# current-source.net
KiCad netlist of a schematic drawn in Altium Designer
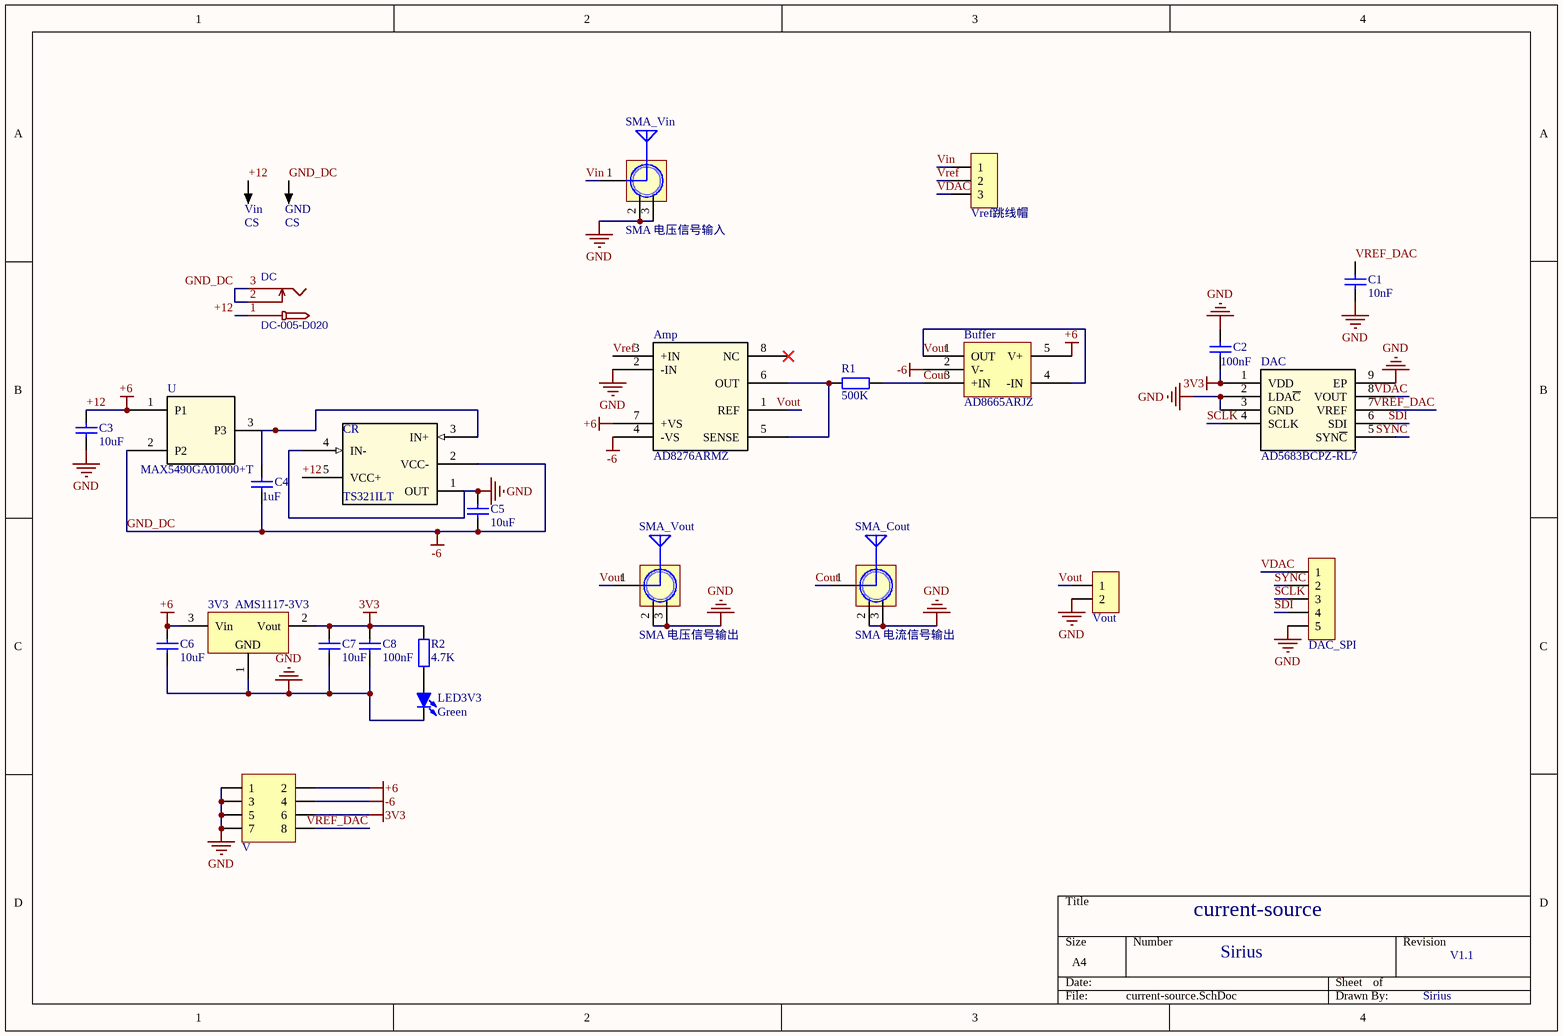
[diagram p0: current-source.SchDoc]

(export (version "E")
  (design (tool "Eeschema 10.0.6"))
  (components
    (comp (ref "3V3")
      (value "AMS1117-3V3")
      (footprint "SOT89_L")
      (description "三端稳压芯片")
      (libsource (lib "0.7 - 电源类芯片") (part "AMS1117_SOT89"))
    )
    (comp (ref "Amp")
      (value "AD8276ARMZ")
      (footprint "RM_8_ADI-L")
      (description "差动放大器")
      (fields
        (field (name "MANUFACTURER_PART_NUMBER") "AD8276ARZ")
        (field (name "COPYRIGHT") "Copyright (C) 2022 Ultra Librarian. All rights reserved.")
      )
      (libsource (lib "Extra Sch") (part "AD8276"))
    )
    (comp (ref "Buffer")
      (value "AD8665ARJZ")
      (footprint "UJ_5_ADI-L")
      (description "低偏置电流运放")
      (libsource (lib "Extra Sch") (part "AD8665ARJZ"))
    )
    (comp (ref "C1")
      (value "10nF")
      (footprint "C0603_L")
      (description "贴片电容")
      (libsource (lib "0.1 - 电阻-电容-电感-晶振-晶体-磁珠-电位器") (part "C"))
    )
    (comp (ref "C2")
      (value "100nF")
      (footprint "C0603_L")
      (description "贴片电容")
      (libsource (lib "0.1 - 电阻-电容-电感-晶振-晶体-磁珠-电位器") (part "C"))
    )
    (comp (ref "C3")
      (value "10uF")
      (footprint "C0603_L")
      (description "贴片电容")
      (libsource (lib "0.1 - 电阻-电容-电感-晶振-晶体-磁珠-电位器") (part "C"))
    )
    (comp (ref "C4")
      (value "1uF")
      (footprint "C0603_L")
      (description "贴片电容")
      (libsource (lib "0.1 - 电阻-电容-电感-晶振-晶体-磁珠-电位器") (part "C"))
    )
    (comp (ref "C5")
      (value "10uF")
      (footprint "C0603_L")
      (description "贴片电容")
      (libsource (lib "0.1 - 电阻-电容-电感-晶振-晶体-磁珠-电位器") (part "C"))
    )
    (comp (ref "C6")
      (value "10uF")
      (footprint "C0603_L")
      (description "贴片电容")
      (libsource (lib "0.1 - 电阻-电容-电感-晶振-晶体-磁珠-电位器") (part "C"))
    )
    (comp (ref "C7")
      (value "10uF")
      (footprint "C0603_L")
      (description "贴片电容")
      (libsource (lib "0.1 - 电阻-电容-电感-晶振-晶体-磁珠-电位器") (part "C"))
    )
    (comp (ref "C8")
      (value "100nF")
      (footprint "C0603_L")
      (description "贴片电容")
      (libsource (lib "0.1 - 电阻-电容-电感-晶振-晶体-磁珠-电位器") (part "C"))
    )
    (comp (ref "CR")
      (value "TS321ILT")
      (footprint "SOT23-5_STM-L")
      (description "Amp")
      (fields (field (name "COPYRIGHT") "Copyright (C) 2022 Ultra Librarian. All rights reserved."))
      (libsource (lib "Extra Sch") (part "TS321ILT"))
    )
    (comp (ref "DAC")
      (value "AD5683BCPZ-RL7")
      (footprint "CP_8_10_ADI-L")
      (description "16bit DAC")
      (fields (field (name "COPYRIGHT") "Copyright (C) 2022 Ultra Librarian. All rights reserved."))
      (libsource (lib "Extra Sch") (part "AD5683BCPZ-RL7"))
    )
    (comp (ref "DAC_SPI")
      (value "HDR-1X5")
      (footprint "XH2.54-WI-5P")
      (description "5P接插件")
      (libsource (lib "5.5 - 2.54mm(100mil)连接器(XH2.54)") (part "Header 5"))
    )
    (comp (ref "DC")
      (value "DC-005-D020")
      (footprint "DC-IN-TH_G-SWITCH_DC-005-D020")
      (fields (field (name "BOM_SUPPLIER PART") "C963210") (field (name "CONTRIBUTOR") "LCSC"))
      (libsource (lib "Extra Sch") (part "DC-005-D020"))
    )
    (comp (ref "GND")
      (value "CS")
      (footprint "R100")
      (description "探针焊盘")
      (libsource (lib "0.5 - 按键-开关-蜂鸣器-保险丝-电池-测试点-Mark点") (part "CS"))
    )
    (comp (ref "LED3V3")
      (value "Green")
      (footprint "LED0603_G")
      (description "贴片LED")
      (libsource (lib "0.3 - LED发光二极管-IR二极管_接收管-光耦") (part "LED-SMD"))
    )
    (comp (ref "R1")
      (value "500K")
      (footprint "R0603_L")
      (description "贴片电阻")
      (libsource (lib "0.1 - 电阻-电容-电感-晶振-晶体-磁珠-电位器") (part "R"))
    )
    (comp (ref "R2")
      (value "4.7K")
      (footprint "R0603_L")
      (description "贴片电阻")
      (libsource (lib "0.1 - 电阻-电容-电感-晶振-晶体-磁珠-电位器") (part "R"))
    )
    (comp (ref "SMA_Cout")
      (value "SMA 电流信号输出")
      (footprint "SMA_FR")
      (description "SMA-2.4G射频天线接口")
      (libsource (lib "1.7 - WiFi天线-SMA射频座") (part "SMA"))
    )
    (comp (ref "SMA_Vin")
      (value "SMA 电压信号输入")
      (footprint "SMA_FR")
      (description "SMA-2.4G射频天线接口")
      (libsource (lib "1.7 - WiFi天线-SMA射频座") (part "SMA"))
    )
    (comp (ref "SMA_Vout")
      (value "SMA 电压信号输出")
      (footprint "SMA_FR")
      (description "SMA-2.4G射频天线接口")
      (libsource (lib "1.7 - WiFi天线-SMA射频座") (part "SMA"))
    )
    (comp (ref "U")
      (value "MAX5490GA01000+T")
      (footprint "21-0051H_MXM-L")
      (description "分压器")
      (fields (field (name "COPYRIGHT") "Copyright (C) 2022 Ultra Librarian. All rights reserved."))
      (libsource (lib "Extra Sch") (part "MAX5490GA01000+T"))
    )
    (comp (ref "V")
      (value "Header 4X2")
      (footprint "HDR2.54-LI-2x4P")
      (description "4*2P接插件")
      (libsource (lib "5.5 - 2.54mm(100mil)连接器(XH2.54)") (part "Header 4X2"))
    )
    (comp (ref "Vin")
      (value "CS")
      (footprint "R100")
      (description "探针焊盘")
      (libsource (lib "0.5 - 按键-开关-蜂鸣器-保险丝-电池-测试点-Mark点") (part "CS"))
    )
    (comp (ref "Vout")
      (value "HDR-1X2")
      (footprint "HDR2.54-LI-2P")
      (description "2P接插件")
      (libsource (lib "5.5 - 2.54mm(100mil)连接器(XH2.54)") (part "Header 2"))
    )
    (comp (ref "Vref跳线帽")
      (value "HDR-1X3")
      (footprint "HDR2.54-LI-3P")
      (description "3P接插件")
      (libsource (lib "5.5 - 2.54mm(100mil)连接器(XH2.54)") (part "Header 3"))
    )
  )
  (nets
    (net (code "1") (name "+6") (class "Default")
      (node (ref "3V3") (pin "3") (pinfunction "Vin_3") (pintype "passive"))
      (node (ref "Amp") (pin "7") (pinfunction "+VS_7") (pintype "passive"))
      (node (ref "Buffer") (pin "5") (pinfunction "V+_5") (pintype "passive"))
      (node (ref "C3") (pin "1") (pinfunction "1_1") (pintype "passive"))
      (node (ref "C6") (pin "2") (pinfunction "2_2") (pintype "passive"))
      (node (ref "CR") (pin "5") (pinfunction "VCC+_5") (pintype "power_in"))
      (node (ref "DC") (pin "1") (pinfunction "1_1") (pintype "passive"))
      (node (ref "U") (pin "1") (pinfunction "P1_1") (pintype "passive"))
      (node (ref "V") (pin "2") (pinfunction "2_2") (pintype "passive"))
      (node (ref "Vin") (pin "1") (pinfunction "1_1") (pintype "passive"))
    )
    (net (code "2") (name "-6") (class "Default")
      (node (ref "Amp") (pin "4") (pinfunction "-VS_4") (pintype "passive"))
      (node (ref "Buffer") (pin "2") (pinfunction "V-_2") (pintype "passive"))
      (node (ref "C4") (pin "1") (pinfunction "1_1") (pintype "passive"))
      (node (ref "C5") (pin "2") (pinfunction "2_2") (pintype "passive"))
      (node (ref "CR") (pin "2") (pinfunction "VCC-_2") (pintype "power_in"))
      (node (ref "DC") (pin "2") (pinfunction "2_2") (pintype "passive"))
      (node (ref "DC") (pin "3") (pinfunction "3_3") (pintype "passive"))
      (node (ref "GND") (pin "1") (pinfunction "1_1") (pintype "passive"))
      (node (ref "U") (pin "2") (pinfunction "P2_2") (pintype "passive"))
      (node (ref "V") (pin "4") (pinfunction "4_4") (pintype "passive"))
    )
    (net (code "3") (name "/Cout") (class "Default")
      (node (ref "Buffer") (pin "3") (pinfunction "+IN_3") (pintype "passive"))
      (node (ref "R1") (pin "1") (pinfunction "1_1") (pintype "passive"))
      (node (ref "SMA_Cout") (pin "1") (pinfunction "ANT_1") (pintype "passive"))
    )
    (net (code "4") (name "/SCLK") (class "Default")
      (node (ref "DAC") (pin "4") (pinfunction "SCLK_4") (pintype "passive"))
      (node (ref "DAC_SPI") (pin "3") (pinfunction "3_3") (pintype "passive"))
    )
    (net (code "5") (name "/SDI") (class "Default")
      (node (ref "DAC") (pin "6") (pinfunction "SDI_6") (pintype "passive"))
      (node (ref "DAC_SPI") (pin "4") (pinfunction "4_4") (pintype "passive"))
    )
    (net (code "6") (name "/SYNC") (class "Default")
      (node (ref "DAC") (pin "5") (pinfunction "SYN~{C}_5") (pintype "passive"))
      (node (ref "DAC_SPI") (pin "2") (pinfunction "2_2") (pintype "passive"))
    )
    (net (code "7") (name "/VDAC") (class "Default")
      (node (ref "DAC") (pin "8") (pinfunction "VOUT_8") (pintype "passive"))
      (node (ref "DAC_SPI") (pin "1") (pinfunction "1_1") (pintype "passive"))
      (node (ref "Vref跳线帽") (pin "3") (pinfunction "3_3") (pintype "passive"))
    )
    (net (code "8") (name "/VREF_DAC") (class "Default")
      (node (ref "C1") (pin "2") (pinfunction "2_2") (pintype "passive"))
      (node (ref "DAC") (pin "7") (pinfunction "VREF_7") (pintype "passive"))
      (node (ref "V") (pin "8") (pinfunction "8_8") (pintype "passive"))
    )
    (net (code "9") (name "/Vin") (class "Default")
      (node (ref "SMA_Vin") (pin "1") (pinfunction "ANT_1") (pintype "passive"))
      (node (ref "Vref跳线帽") (pin "1") (pinfunction "1_1") (pintype "passive"))
    )
    (net (code "10") (name "/Vout") (class "Default")
      (node (ref "Amp") (pin "1") (pinfunction "REF_1") (pintype "passive"))
      (node (ref "Buffer") (pin "1") (pinfunction "OUT_1") (pintype "passive"))
      (node (ref "Buffer") (pin "4") (pinfunction "-IN_4") (pintype "passive"))
      (node (ref "SMA_Vout") (pin "1") (pinfunction "ANT_1") (pintype "passive"))
      (node (ref "Vout") (pin "1") (pinfunction "1_1") (pintype "passive"))
    )
    (net (code "11") (name "/Vref") (class "Default")
      (node (ref "Amp") (pin "3") (pinfunction "+IN_3") (pintype "passive"))
      (node (ref "Vref跳线帽") (pin "2") (pinfunction "2_2") (pintype "passive"))
    )
    (net (code "12") (name "3V3") (class "Default")
      (node (ref "3V3") (pin "2") (pinfunction "Vout_2") (pintype "passive"))
      (node (ref "C2") (pin "1") (pinfunction "1_1") (pintype "passive"))
      (node (ref "C7") (pin "2") (pinfunction "2_2") (pintype "passive"))
      (node (ref "C8") (pin "2") (pinfunction "2_2") (pintype "passive"))
      (node (ref "DAC") (pin "1") (pinfunction "VDD_1") (pintype "passive"))
      (node (ref "R2") (pin "2") (pinfunction "2_2") (pintype "passive"))
      (node (ref "V") (pin "6") (pinfunction "6_6") (pintype "passive"))
    )
    (net (code "13") (name "GND") (class "Default")
      (node (ref "3V3") (pin "1") (pinfunction "GND_1") (pintype "passive"))
      (node (ref "Amp") (pin "2") (pinfunction "-IN_2") (pintype "passive"))
      (node (ref "C1") (pin "1") (pinfunction "1_1") (pintype "passive"))
      (node (ref "C2") (pin "2") (pinfunction "2_2") (pintype "passive"))
      (node (ref "C3") (pin "2") (pinfunction "2_2") (pintype "passive"))
      (node (ref "C5") (pin "1") (pinfunction "1_1") (pintype "passive"))
      (node (ref "C6") (pin "1") (pinfunction "1_1") (pintype "passive"))
      (node (ref "C7") (pin "1") (pinfunction "1_1") (pintype "passive"))
      (node (ref "C8") (pin "1") (pinfunction "1_1") (pintype "passive"))
      (node (ref "CR") (pin "1") (pinfunction "OUT_1") (pintype "passive"))
      (node (ref "CR") (pin "4") (pinfunction "IN-_4") (pintype "input"))
      (node (ref "DAC") (pin "2") (pinfunction "LDA~{C}_2") (pintype "passive"))
      (node (ref "DAC") (pin "3") (pinfunction "GND_3") (pintype "passive"))
      (node (ref "DAC") (pin "9") (pinfunction "EP_9") (pintype "passive"))
      (node (ref "DAC_SPI") (pin "5") (pinfunction "5_5") (pintype "passive"))
      (node (ref "LED3V3") (pin "2") (pinfunction "K_2") (pintype "passive"))
      (node (ref "SMA_Cout") (pin "2") (pinfunction "GND_2") (pintype "passive"))
      (node (ref "SMA_Cout") (pin "3") (pinfunction "GND_3") (pintype "passive"))
      (node (ref "SMA_Vin") (pin "2") (pinfunction "GND_2") (pintype "passive"))
      (node (ref "SMA_Vin") (pin "3") (pinfunction "GND_3") (pintype "passive"))
      (node (ref "SMA_Vout") (pin "2") (pinfunction "GND_2") (pintype "passive"))
      (node (ref "SMA_Vout") (pin "3") (pinfunction "GND_3") (pintype "passive"))
      (node (ref "V") (pin "1") (pinfunction "1_1") (pintype "passive"))
      (node (ref "V") (pin "3") (pinfunction "3_3") (pintype "passive"))
      (node (ref "V") (pin "5") (pinfunction "5_5") (pintype "passive"))
      (node (ref "V") (pin "7") (pinfunction "7_7") (pintype "passive"))
      (node (ref "Vout") (pin "2") (pinfunction "2_2") (pintype "passive"))
    )
    (net (code "14") (name "Net-(Amp-OUT)") (class "Default")
      (node (ref "Amp") (pin "5") (pinfunction "SENSE_5") (pintype "passive"))
      (node (ref "Amp") (pin "6") (pinfunction "OUT_6") (pintype "passive"))
      (node (ref "R1") (pin "2") (pinfunction "2_2") (pintype "passive"))
    )
    (net (code "15") (name "Net-(CR-IN+)") (class "Default")
      (node (ref "C4") (pin "2") (pinfunction "2_2") (pintype "passive"))
      (node (ref "CR") (pin "3") (pinfunction "IN+_3") (pintype "input"))
      (node (ref "U") (pin "3") (pinfunction "P3_3") (pintype "passive"))
    )
    (net (code "16") (name "Net-(LED3V3-A)") (class "Default")
      (node (ref "LED3V3") (pin "1") (pinfunction "A_1") (pintype "passive"))
      (node (ref "R2") (pin "1") (pinfunction "1_1") (pintype "passive"))
    )
    (net (code "17") (name "unconnected-(Amp-NC-Pad8)") (class "Default")
      (node (ref "Amp") (pin "8") (pinfunction "NC_8") (pintype "passive+no_connect"))
    )
  )
)
